# main.net
KiCad netlist of a schematic drawn in EAGLE
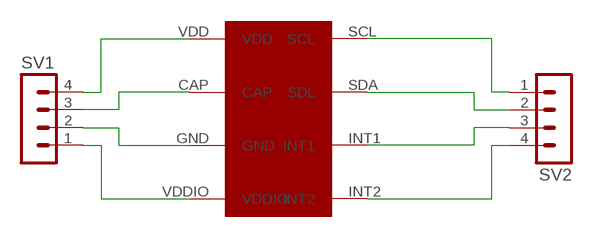
[diagram p0: schematic, sheet 1]

(export (version "E")
  (design (tool "Eeschema 10.0.6"))
  (components
    (comp (ref "SV1")
      (value "MA04-1")
      (footprint "eagle-import:MA04-1")
      (libsource (lib "eagle-import") (part "MA04-1"))
    )
    (comp (ref "SV2")
      (value "MA04-1")
      (footprint "eagle-import:MA04-1")
      (libsource (lib "eagle-import") (part "MA04-1"))
    )
    (comp (ref "U$1")
      (value "MPL3115A2")
      (footprint "eagle-import:LGA8_CAN")
      (libsource (lib "eagle-import") (part "MPL3115A2"))
    )
  )
  (nets
    (net (code "1") (name "Net-(SV1-Pad1)") (class "Default")
      (node (ref "SV1") (pin "1") (pinfunction "1_1") (pintype "passive"))
      (node (ref "U$1") (pin "VDDIO") (pinfunction "VDDIO_VDDIO") (pintype "bidirectional"))
    )
    (net (code "2") (name "Net-(SV1-Pad2)") (class "Default")
      (node (ref "SV1") (pin "2") (pinfunction "2_2") (pintype "passive"))
      (node (ref "U$1") (pin "GND") (pinfunction "GND_GND") (pintype "bidirectional"))
    )
    (net (code "3") (name "Net-(SV1-Pad3)") (class "Default")
      (node (ref "SV1") (pin "3") (pinfunction "3_3") (pintype "passive"))
      (node (ref "U$1") (pin "CAP") (pinfunction "CAP_CAP") (pintype "bidirectional"))
    )
    (net (code "4") (name "Net-(SV1-Pad4)") (class "Default")
      (node (ref "SV1") (pin "4") (pinfunction "4_4") (pintype "passive"))
      (node (ref "U$1") (pin "VDD") (pinfunction "VDD_VDD") (pintype "bidirectional"))
    )
    (net (code "5") (name "Net-(SV2-Pad1)") (class "Default")
      (node (ref "SV2") (pin "1") (pinfunction "1_1") (pintype "passive"))
      (node (ref "U$1") (pin "SCL") (pinfunction "SCL_SCL") (pintype "bidirectional"))
    )
    (net (code "6") (name "Net-(SV2-Pad3)") (class "Default")
      (node (ref "SV2") (pin "3") (pinfunction "3_3") (pintype "passive"))
      (node (ref "U$1") (pin "INT1") (pinfunction "INT1_INT1") (pintype "bidirectional"))
    )
    (net (code "7") (name "Net-(SV2-Pad4)") (class "Default")
      (node (ref "SV2") (pin "4") (pinfunction "4_4") (pintype "passive"))
      (node (ref "U$1") (pin "INT2") (pinfunction "INT2_INT2") (pintype "bidirectional"))
    )
    (net (code "8") (name "Net-(U$1-SDL)") (class "Default")
      (node (ref "SV2") (pin "2") (pinfunction "2_2") (pintype "passive"))
      (node (ref "U$1") (pin "SDA") (pinfunction "SDL_SDA") (pintype "bidirectional"))
    )
  )
)
